# line-board.net
KiCad netlist of a schematic drawn in EAGLE
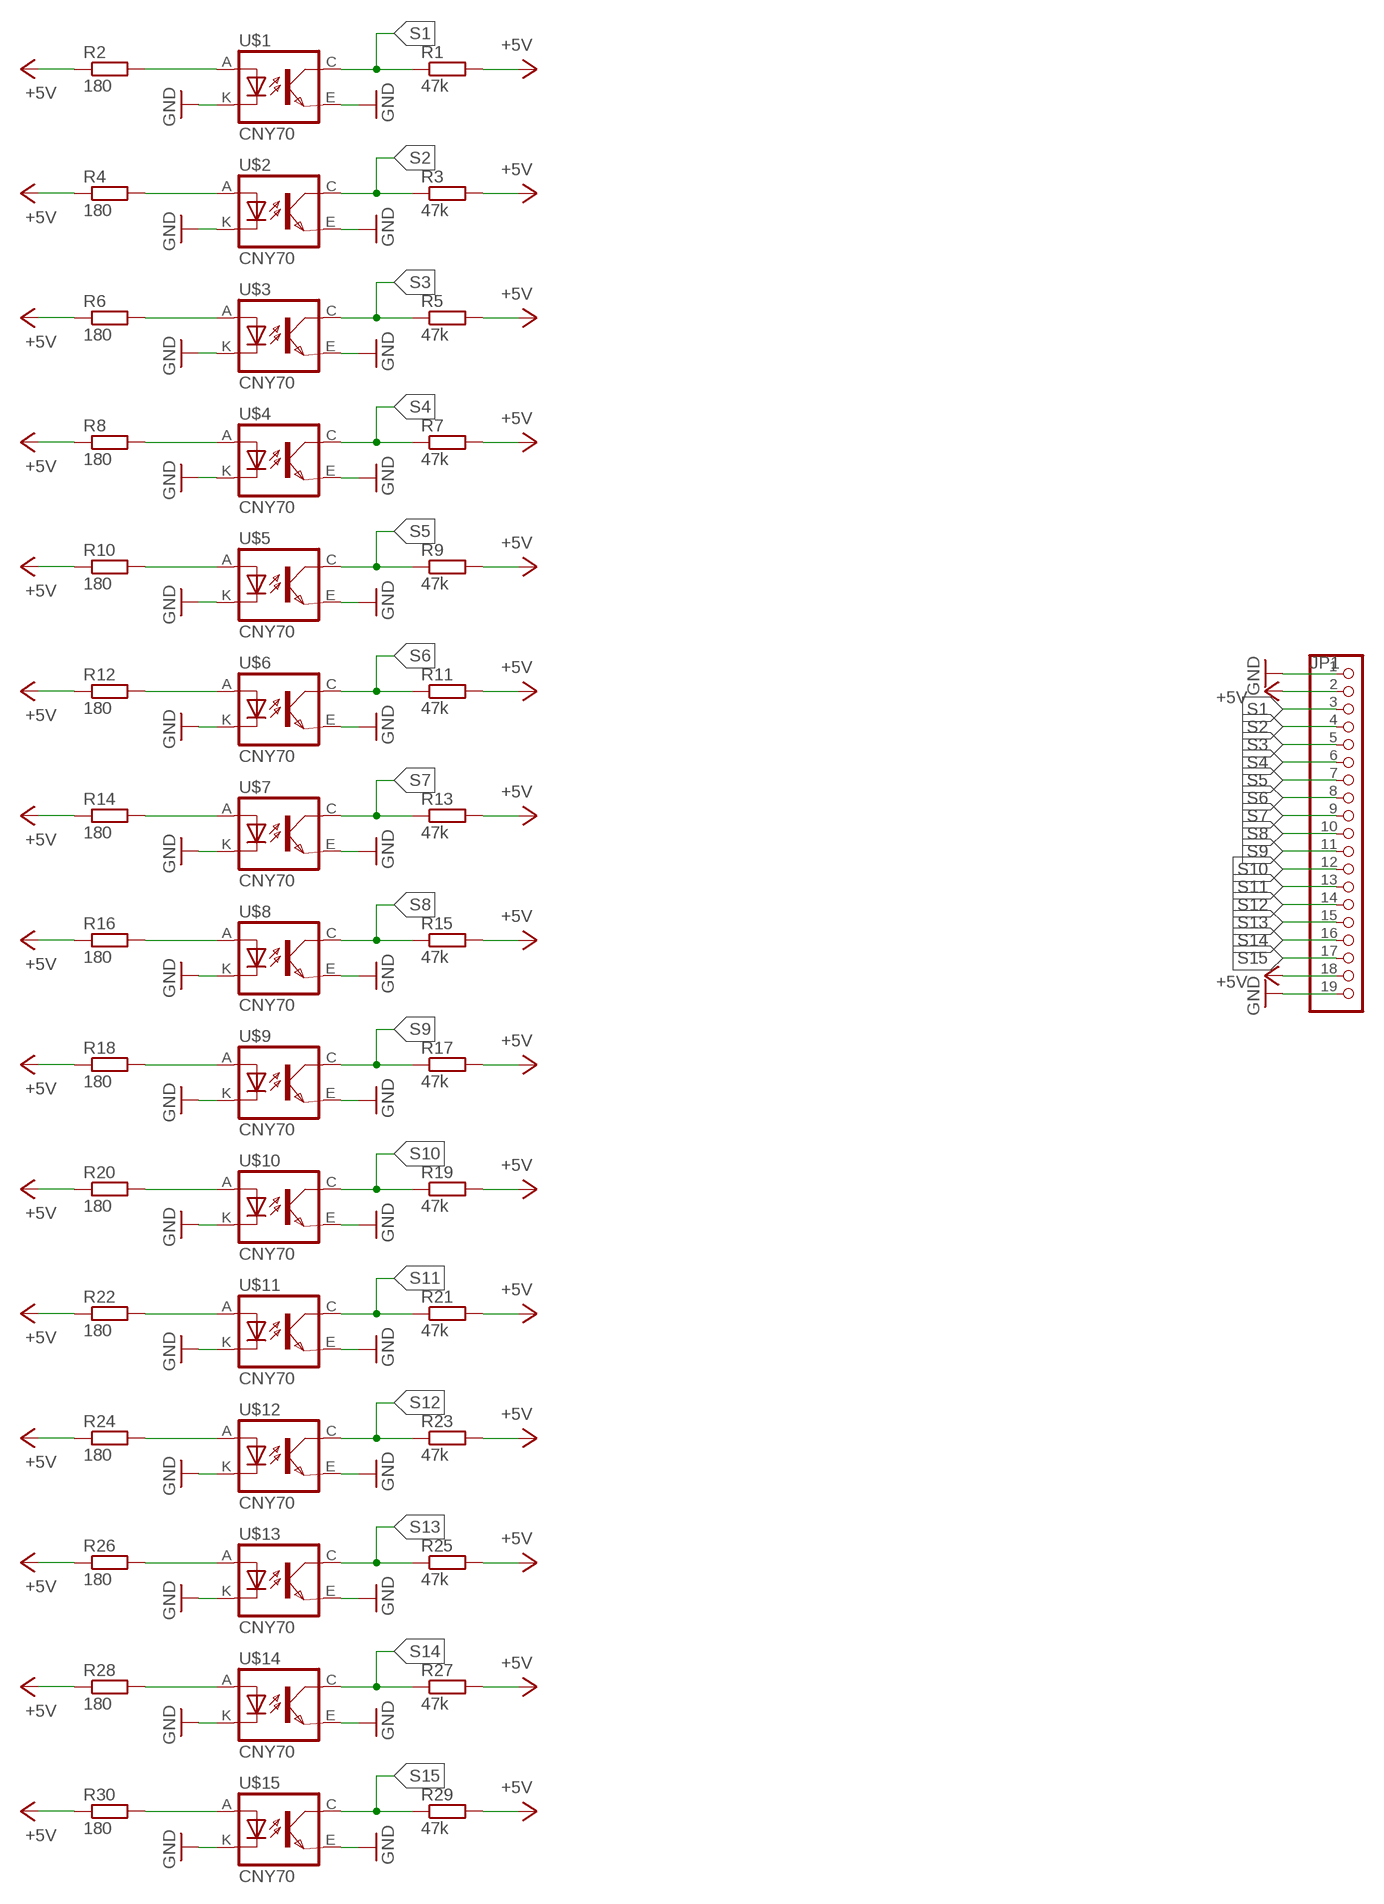
[diagram p0: schematic, sheet 1]

(export (version "E")
  (design (tool "Eeschema 10.0.6"))
  (components
    (comp (ref "JP1")
      (value "PINHD-1X19")
      (footprint "eagle-import:1X19")
      (libsource (lib "eagle-import") (part "PINHD-1X19"))
    )
    (comp (ref "R1")
      (value "47k")
      (footprint "eagle-import:R1206")
      (libsource (lib "eagle-import") (part "R-EU_R1206"))
    )
    (comp (ref "R2")
      (value "180")
      (footprint "eagle-import:R1206")
      (libsource (lib "eagle-import") (part "R-EU_R1206"))
    )
    (comp (ref "R3")
      (value "47k")
      (footprint "eagle-import:R1206")
      (libsource (lib "eagle-import") (part "R-EU_R1206"))
    )
    (comp (ref "R4")
      (value "180")
      (footprint "eagle-import:R1206")
      (libsource (lib "eagle-import") (part "R-EU_R1206"))
    )
    (comp (ref "R5")
      (value "47k")
      (footprint "eagle-import:R1206")
      (libsource (lib "eagle-import") (part "R-EU_R1206"))
    )
    (comp (ref "R6")
      (value "180")
      (footprint "eagle-import:R1206")
      (libsource (lib "eagle-import") (part "R-EU_R1206"))
    )
    (comp (ref "R7")
      (value "47k")
      (footprint "eagle-import:R1206")
      (libsource (lib "eagle-import") (part "R-EU_R1206"))
    )
    (comp (ref "R8")
      (value "180")
      (footprint "eagle-import:R1206")
      (libsource (lib "eagle-import") (part "R-EU_R1206"))
    )
    (comp (ref "R9")
      (value "47k")
      (footprint "eagle-import:R1206")
      (libsource (lib "eagle-import") (part "R-EU_R1206"))
    )
    (comp (ref "R10")
      (value "180")
      (footprint "eagle-import:R1206")
      (libsource (lib "eagle-import") (part "R-EU_R1206"))
    )
    (comp (ref "R11")
      (value "47k")
      (footprint "eagle-import:R1206")
      (libsource (lib "eagle-import") (part "R-EU_R1206"))
    )
    (comp (ref "R12")
      (value "180")
      (footprint "eagle-import:R1206")
      (libsource (lib "eagle-import") (part "R-EU_R1206"))
    )
    (comp (ref "R13")
      (value "47k")
      (footprint "eagle-import:R1206")
      (libsource (lib "eagle-import") (part "R-EU_R1206"))
    )
    (comp (ref "R14")
      (value "180")
      (footprint "eagle-import:R1206")
      (libsource (lib "eagle-import") (part "R-EU_R1206"))
    )
    (comp (ref "R15")
      (value "47k")
      (footprint "eagle-import:R1206")
      (libsource (lib "eagle-import") (part "R-EU_R1206"))
    )
    (comp (ref "R16")
      (value "180")
      (footprint "eagle-import:R1206")
      (libsource (lib "eagle-import") (part "R-EU_R1206"))
    )
    (comp (ref "R17")
      (value "47k")
      (footprint "eagle-import:R1206")
      (libsource (lib "eagle-import") (part "R-EU_R1206"))
    )
    (comp (ref "R18")
      (value "180")
      (footprint "eagle-import:R1206")
      (libsource (lib "eagle-import") (part "R-EU_R1206"))
    )
    (comp (ref "R19")
      (value "47k")
      (footprint "eagle-import:R1206")
      (libsource (lib "eagle-import") (part "R-EU_R1206"))
    )
    (comp (ref "R20")
      (value "180")
      (footprint "eagle-import:R1206")
      (libsource (lib "eagle-import") (part "R-EU_R1206"))
    )
    (comp (ref "R21")
      (value "47k")
      (footprint "eagle-import:R1206")
      (libsource (lib "eagle-import") (part "R-EU_R1206"))
    )
    (comp (ref "R22")
      (value "180")
      (footprint "eagle-import:R1206")
      (libsource (lib "eagle-import") (part "R-EU_R1206"))
    )
    (comp (ref "R23")
      (value "47k")
      (footprint "eagle-import:R1206")
      (libsource (lib "eagle-import") (part "R-EU_R1206"))
    )
    (comp (ref "R24")
      (value "180")
      (footprint "eagle-import:R1206")
      (libsource (lib "eagle-import") (part "R-EU_R1206"))
    )
    (comp (ref "R25")
      (value "47k")
      (footprint "eagle-import:R1206")
      (libsource (lib "eagle-import") (part "R-EU_R1206"))
    )
    (comp (ref "R26")
      (value "180")
      (footprint "eagle-import:R1206")
      (libsource (lib "eagle-import") (part "R-EU_R1206"))
    )
    (comp (ref "R27")
      (value "47k")
      (footprint "eagle-import:R1206")
      (libsource (lib "eagle-import") (part "R-EU_R1206"))
    )
    (comp (ref "R28")
      (value "180")
      (footprint "eagle-import:R1206")
      (libsource (lib "eagle-import") (part "R-EU_R1206"))
    )
    (comp (ref "R29")
      (value "47k")
      (footprint "eagle-import:R1206")
      (libsource (lib "eagle-import") (part "R-EU_R1206"))
    )
    (comp (ref "R30")
      (value "180")
      (footprint "eagle-import:R1206")
      (libsource (lib "eagle-import") (part "R-EU_R1206"))
    )
    (comp (ref "U$1")
      (value "CNY70")
      (footprint "eagle-import:4")
      (libsource (lib "eagle-import") (part "CNY70"))
    )
    (comp (ref "U$2")
      (value "CNY70")
      (footprint "eagle-import:4")
      (libsource (lib "eagle-import") (part "CNY70"))
    )
    (comp (ref "U$3")
      (value "CNY70")
      (footprint "eagle-import:4")
      (libsource (lib "eagle-import") (part "CNY70"))
    )
    (comp (ref "U$4")
      (value "CNY70")
      (footprint "eagle-import:4")
      (libsource (lib "eagle-import") (part "CNY70"))
    )
    (comp (ref "U$5")
      (value "CNY70")
      (footprint "eagle-import:4")
      (libsource (lib "eagle-import") (part "CNY70"))
    )
    (comp (ref "U$6")
      (value "CNY70")
      (footprint "eagle-import:4")
      (libsource (lib "eagle-import") (part "CNY70"))
    )
    (comp (ref "U$7")
      (value "CNY70")
      (footprint "eagle-import:4")
      (libsource (lib "eagle-import") (part "CNY70"))
    )
    (comp (ref "U$8")
      (value "CNY70")
      (footprint "eagle-import:4")
      (libsource (lib "eagle-import") (part "CNY70"))
    )
    (comp (ref "U$9")
      (value "CNY70")
      (footprint "eagle-import:4")
      (libsource (lib "eagle-import") (part "CNY70"))
    )
    (comp (ref "U$10")
      (value "CNY70")
      (footprint "eagle-import:4")
      (libsource (lib "eagle-import") (part "CNY70"))
    )
    (comp (ref "U$11")
      (value "CNY70")
      (footprint "eagle-import:4")
      (libsource (lib "eagle-import") (part "CNY70"))
    )
    (comp (ref "U$12")
      (value "CNY70")
      (footprint "eagle-import:4")
      (libsource (lib "eagle-import") (part "CNY70"))
    )
    (comp (ref "U$13")
      (value "CNY70")
      (footprint "eagle-import:4")
      (libsource (lib "eagle-import") (part "CNY70"))
    )
    (comp (ref "U$14")
      (value "CNY70")
      (footprint "eagle-import:4")
      (libsource (lib "eagle-import") (part "CNY70"))
    )
    (comp (ref "U$15")
      (value "CNY70")
      (footprint "eagle-import:4")
      (libsource (lib "eagle-import") (part "CNY70"))
    )
  )
  (nets
    (net (code "1") (name "+5V") (class "Default")
      (node (ref "JP1") (pin "18") (pinfunction "18_18") (pintype "passive"))
      (node (ref "JP1") (pin "2") (pinfunction "2_2") (pintype "passive"))
      (node (ref "R1") (pin "2") (pinfunction "2_2") (pintype "passive"))
      (node (ref "R10") (pin "1") (pinfunction "1_1") (pintype "passive"))
      (node (ref "R11") (pin "2") (pinfunction "2_2") (pintype "passive"))
      (node (ref "R12") (pin "1") (pinfunction "1_1") (pintype "passive"))
      (node (ref "R13") (pin "2") (pinfunction "2_2") (pintype "passive"))
      (node (ref "R14") (pin "1") (pinfunction "1_1") (pintype "passive"))
      (node (ref "R15") (pin "2") (pinfunction "2_2") (pintype "passive"))
      (node (ref "R16") (pin "1") (pinfunction "1_1") (pintype "passive"))
      (node (ref "R17") (pin "2") (pinfunction "2_2") (pintype "passive"))
      (node (ref "R18") (pin "1") (pinfunction "1_1") (pintype "passive"))
      (node (ref "R19") (pin "2") (pinfunction "2_2") (pintype "passive"))
      (node (ref "R2") (pin "1") (pinfunction "1_1") (pintype "passive"))
      (node (ref "R20") (pin "1") (pinfunction "1_1") (pintype "passive"))
      (node (ref "R21") (pin "2") (pinfunction "2_2") (pintype "passive"))
      (node (ref "R22") (pin "1") (pinfunction "1_1") (pintype "passive"))
      (node (ref "R23") (pin "2") (pinfunction "2_2") (pintype "passive"))
      (node (ref "R24") (pin "1") (pinfunction "1_1") (pintype "passive"))
      (node (ref "R25") (pin "2") (pinfunction "2_2") (pintype "passive"))
      (node (ref "R26") (pin "1") (pinfunction "1_1") (pintype "passive"))
      (node (ref "R27") (pin "2") (pinfunction "2_2") (pintype "passive"))
      (node (ref "R28") (pin "1") (pinfunction "1_1") (pintype "passive"))
      (node (ref "R29") (pin "2") (pinfunction "2_2") (pintype "passive"))
      (node (ref "R3") (pin "2") (pinfunction "2_2") (pintype "passive"))
      (node (ref "R30") (pin "1") (pinfunction "1_1") (pintype "passive"))
      (node (ref "R4") (pin "1") (pinfunction "1_1") (pintype "passive"))
      (node (ref "R5") (pin "2") (pinfunction "2_2") (pintype "passive"))
      (node (ref "R6") (pin "1") (pinfunction "1_1") (pintype "passive"))
      (node (ref "R7") (pin "2") (pinfunction "2_2") (pintype "passive"))
      (node (ref "R8") (pin "1") (pinfunction "1_1") (pintype "passive"))
      (node (ref "R9") (pin "2") (pinfunction "2_2") (pintype "passive"))
    )
    (net (code "2") (name "GND") (class "Default")
      (node (ref "JP1") (pin "1") (pinfunction "1_1") (pintype "passive"))
      (node (ref "JP1") (pin "19") (pinfunction "19_19") (pintype "passive"))
      (node (ref "U$1") (pin "E") (pinfunction "EMI_E") (pintype "passive"))
      (node (ref "U$1") (pin "K") (pinfunction "C_K") (pintype "passive"))
      (node (ref "U$10") (pin "E") (pinfunction "EMI_E") (pintype "passive"))
      (node (ref "U$10") (pin "K") (pinfunction "C_K") (pintype "passive"))
      (node (ref "U$11") (pin "E") (pinfunction "EMI_E") (pintype "passive"))
      (node (ref "U$11") (pin "K") (pinfunction "C_K") (pintype "passive"))
      (node (ref "U$12") (pin "E") (pinfunction "EMI_E") (pintype "passive"))
      (node (ref "U$12") (pin "K") (pinfunction "C_K") (pintype "passive"))
      (node (ref "U$13") (pin "E") (pinfunction "EMI_E") (pintype "passive"))
      (node (ref "U$13") (pin "K") (pinfunction "C_K") (pintype "passive"))
      (node (ref "U$14") (pin "E") (pinfunction "EMI_E") (pintype "passive"))
      (node (ref "U$14") (pin "K") (pinfunction "C_K") (pintype "passive"))
      (node (ref "U$15") (pin "E") (pinfunction "EMI_E") (pintype "passive"))
      (node (ref "U$15") (pin "K") (pinfunction "C_K") (pintype "passive"))
      (node (ref "U$2") (pin "E") (pinfunction "EMI_E") (pintype "passive"))
      (node (ref "U$2") (pin "K") (pinfunction "C_K") (pintype "passive"))
      (node (ref "U$3") (pin "E") (pinfunction "EMI_E") (pintype "passive"))
      (node (ref "U$3") (pin "K") (pinfunction "C_K") (pintype "passive"))
      (node (ref "U$4") (pin "E") (pinfunction "EMI_E") (pintype "passive"))
      (node (ref "U$4") (pin "K") (pinfunction "C_K") (pintype "passive"))
      (node (ref "U$5") (pin "E") (pinfunction "EMI_E") (pintype "passive"))
      (node (ref "U$5") (pin "K") (pinfunction "C_K") (pintype "passive"))
      (node (ref "U$6") (pin "E") (pinfunction "EMI_E") (pintype "passive"))
      (node (ref "U$6") (pin "K") (pinfunction "C_K") (pintype "passive"))
      (node (ref "U$7") (pin "E") (pinfunction "EMI_E") (pintype "passive"))
      (node (ref "U$7") (pin "K") (pinfunction "C_K") (pintype "passive"))
      (node (ref "U$8") (pin "E") (pinfunction "EMI_E") (pintype "passive"))
      (node (ref "U$8") (pin "K") (pinfunction "C_K") (pintype "passive"))
      (node (ref "U$9") (pin "E") (pinfunction "EMI_E") (pintype "passive"))
      (node (ref "U$9") (pin "K") (pinfunction "C_K") (pintype "passive"))
    )
    (net (code "3") (name "Net-(R2-Pad2)") (class "Default")
      (node (ref "R2") (pin "2") (pinfunction "2_2") (pintype "passive"))
      (node (ref "U$1") (pin "A") (pinfunction "A_A") (pintype "passive"))
    )
    (net (code "4") (name "Net-(R4-Pad2)") (class "Default")
      (node (ref "R4") (pin "2") (pinfunction "2_2") (pintype "passive"))
      (node (ref "U$2") (pin "A") (pinfunction "A_A") (pintype "passive"))
    )
    (net (code "5") (name "Net-(R6-Pad2)") (class "Default")
      (node (ref "R6") (pin "2") (pinfunction "2_2") (pintype "passive"))
      (node (ref "U$3") (pin "A") (pinfunction "A_A") (pintype "passive"))
    )
    (net (code "6") (name "Net-(R8-Pad2)") (class "Default")
      (node (ref "R8") (pin "2") (pinfunction "2_2") (pintype "passive"))
      (node (ref "U$4") (pin "A") (pinfunction "A_A") (pintype "passive"))
    )
    (net (code "7") (name "Net-(R10-Pad2)") (class "Default")
      (node (ref "R10") (pin "2") (pinfunction "2_2") (pintype "passive"))
      (node (ref "U$5") (pin "A") (pinfunction "A_A") (pintype "passive"))
    )
    (net (code "8") (name "Net-(R12-Pad2)") (class "Default")
      (node (ref "R12") (pin "2") (pinfunction "2_2") (pintype "passive"))
      (node (ref "U$6") (pin "A") (pinfunction "A_A") (pintype "passive"))
    )
    (net (code "9") (name "Net-(R14-Pad2)") (class "Default")
      (node (ref "R14") (pin "2") (pinfunction "2_2") (pintype "passive"))
      (node (ref "U$7") (pin "A") (pinfunction "A_A") (pintype "passive"))
    )
    (net (code "10") (name "Net-(R16-Pad2)") (class "Default")
      (node (ref "R16") (pin "2") (pinfunction "2_2") (pintype "passive"))
      (node (ref "U$8") (pin "A") (pinfunction "A_A") (pintype "passive"))
    )
    (net (code "11") (name "Net-(R18-Pad2)") (class "Default")
      (node (ref "R18") (pin "2") (pinfunction "2_2") (pintype "passive"))
      (node (ref "U$9") (pin "A") (pinfunction "A_A") (pintype "passive"))
    )
    (net (code "12") (name "Net-(R20-Pad2)") (class "Default")
      (node (ref "R20") (pin "2") (pinfunction "2_2") (pintype "passive"))
      (node (ref "U$10") (pin "A") (pinfunction "A_A") (pintype "passive"))
    )
    (net (code "13") (name "Net-(R22-Pad2)") (class "Default")
      (node (ref "R22") (pin "2") (pinfunction "2_2") (pintype "passive"))
      (node (ref "U$11") (pin "A") (pinfunction "A_A") (pintype "passive"))
    )
    (net (code "14") (name "Net-(R24-Pad2)") (class "Default")
      (node (ref "R24") (pin "2") (pinfunction "2_2") (pintype "passive"))
      (node (ref "U$12") (pin "A") (pinfunction "A_A") (pintype "passive"))
    )
    (net (code "15") (name "Net-(R26-Pad2)") (class "Default")
      (node (ref "R26") (pin "2") (pinfunction "2_2") (pintype "passive"))
      (node (ref "U$13") (pin "A") (pinfunction "A_A") (pintype "passive"))
    )
    (net (code "16") (name "Net-(R28-Pad2)") (class "Default")
      (node (ref "R28") (pin "2") (pinfunction "2_2") (pintype "passive"))
      (node (ref "U$14") (pin "A") (pinfunction "A_A") (pintype "passive"))
    )
    (net (code "17") (name "Net-(R30-Pad2)") (class "Default")
      (node (ref "R30") (pin "2") (pinfunction "2_2") (pintype "passive"))
      (node (ref "U$15") (pin "A") (pinfunction "A_A") (pintype "passive"))
    )
    (net (code "18") (name "S1") (class "Default")
      (node (ref "JP1") (pin "3") (pinfunction "3_3") (pintype "passive"))
      (node (ref "R1") (pin "1") (pinfunction "1_1") (pintype "passive"))
      (node (ref "U$1") (pin "C") (pinfunction "COL_C") (pintype "passive"))
    )
    (net (code "19") (name "S2") (class "Default")
      (node (ref "JP1") (pin "4") (pinfunction "4_4") (pintype "passive"))
      (node (ref "R3") (pin "1") (pinfunction "1_1") (pintype "passive"))
      (node (ref "U$2") (pin "C") (pinfunction "COL_C") (pintype "passive"))
    )
    (net (code "20") (name "S3") (class "Default")
      (node (ref "JP1") (pin "5") (pinfunction "5_5") (pintype "passive"))
      (node (ref "R5") (pin "1") (pinfunction "1_1") (pintype "passive"))
      (node (ref "U$3") (pin "C") (pinfunction "COL_C") (pintype "passive"))
    )
    (net (code "21") (name "S4") (class "Default")
      (node (ref "JP1") (pin "6") (pinfunction "6_6") (pintype "passive"))
      (node (ref "R7") (pin "1") (pinfunction "1_1") (pintype "passive"))
      (node (ref "U$4") (pin "C") (pinfunction "COL_C") (pintype "passive"))
    )
    (net (code "22") (name "S5") (class "Default")
      (node (ref "JP1") (pin "7") (pinfunction "7_7") (pintype "passive"))
      (node (ref "R9") (pin "1") (pinfunction "1_1") (pintype "passive"))
      (node (ref "U$5") (pin "C") (pinfunction "COL_C") (pintype "passive"))
    )
    (net (code "23") (name "S6") (class "Default")
      (node (ref "JP1") (pin "8") (pinfunction "8_8") (pintype "passive"))
      (node (ref "R11") (pin "1") (pinfunction "1_1") (pintype "passive"))
      (node (ref "U$6") (pin "C") (pinfunction "COL_C") (pintype "passive"))
    )
    (net (code "24") (name "S7") (class "Default")
      (node (ref "JP1") (pin "9") (pinfunction "9_9") (pintype "passive"))
      (node (ref "R13") (pin "1") (pinfunction "1_1") (pintype "passive"))
      (node (ref "U$7") (pin "C") (pinfunction "COL_C") (pintype "passive"))
    )
    (net (code "25") (name "S8") (class "Default")
      (node (ref "JP1") (pin "10") (pinfunction "10_10") (pintype "passive"))
      (node (ref "R15") (pin "1") (pinfunction "1_1") (pintype "passive"))
      (node (ref "U$8") (pin "C") (pinfunction "COL_C") (pintype "passive"))
    )
    (net (code "26") (name "S9") (class "Default")
      (node (ref "JP1") (pin "11") (pinfunction "11_11") (pintype "passive"))
      (node (ref "R17") (pin "1") (pinfunction "1_1") (pintype "passive"))
      (node (ref "U$9") (pin "C") (pinfunction "COL_C") (pintype "passive"))
    )
    (net (code "27") (name "S10") (class "Default")
      (node (ref "JP1") (pin "12") (pinfunction "12_12") (pintype "passive"))
      (node (ref "R19") (pin "1") (pinfunction "1_1") (pintype "passive"))
      (node (ref "U$10") (pin "C") (pinfunction "COL_C") (pintype "passive"))
    )
    (net (code "28") (name "S11") (class "Default")
      (node (ref "JP1") (pin "13") (pinfunction "13_13") (pintype "passive"))
      (node (ref "R21") (pin "1") (pinfunction "1_1") (pintype "passive"))
      (node (ref "U$11") (pin "C") (pinfunction "COL_C") (pintype "passive"))
    )
    (net (code "29") (name "S12") (class "Default")
      (node (ref "JP1") (pin "14") (pinfunction "14_14") (pintype "passive"))
      (node (ref "R23") (pin "1") (pinfunction "1_1") (pintype "passive"))
      (node (ref "U$12") (pin "C") (pinfunction "COL_C") (pintype "passive"))
    )
    (net (code "30") (name "S13") (class "Default")
      (node (ref "JP1") (pin "15") (pinfunction "15_15") (pintype "passive"))
      (node (ref "R25") (pin "1") (pinfunction "1_1") (pintype "passive"))
      (node (ref "U$13") (pin "C") (pinfunction "COL_C") (pintype "passive"))
    )
    (net (code "31") (name "S14") (class "Default")
      (node (ref "JP1") (pin "16") (pinfunction "16_16") (pintype "passive"))
      (node (ref "R27") (pin "1") (pinfunction "1_1") (pintype "passive"))
      (node (ref "U$14") (pin "C") (pinfunction "COL_C") (pintype "passive"))
    )
    (net (code "32") (name "S15") (class "Default")
      (node (ref "JP1") (pin "17") (pinfunction "17_17") (pintype "passive"))
      (node (ref "R29") (pin "1") (pinfunction "1_1") (pintype "passive"))
      (node (ref "U$15") (pin "C") (pinfunction "COL_C") (pintype "passive"))
    )
  )
)
